# audiomeaskit.net
KiCad netlist of a schematic drawn in EAGLE
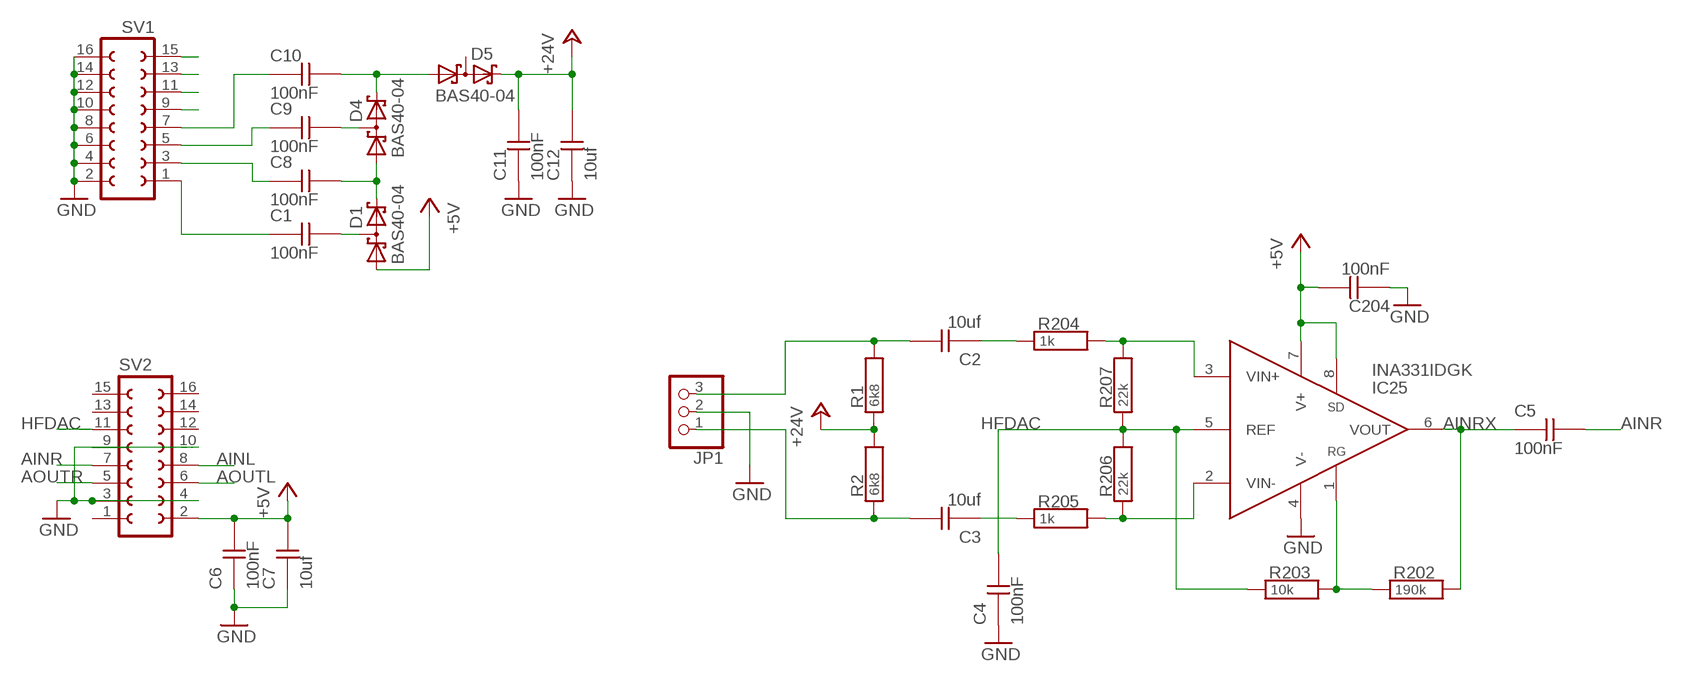
[diagram p0: schematic, sheet 1]

(export (version "E")
  (design (tool "Eeschema 10.0.6"))
  (components
    (comp (ref "C1")
      (value "100nF")
      (footprint "eagle-import:0603")
      (libsource (lib "eagle-import") (part "CAPC0603"))
    )
    (comp (ref "C2")
      (value "10uf")
      (footprint "eagle-import:0805")
      (libsource (lib "eagle-import") (part "CAPC0805"))
    )
    (comp (ref "C3")
      (value "10uf")
      (footprint "eagle-import:0805")
      (libsource (lib "eagle-import") (part "CAPC0805"))
    )
    (comp (ref "C4")
      (value "100nF")
      (footprint "eagle-import:0603")
      (libsource (lib "eagle-import") (part "CAPC0603"))
    )
    (comp (ref "C5")
      (value "100nF")
      (footprint "eagle-import:0603")
      (libsource (lib "eagle-import") (part "CAPC0603"))
    )
    (comp (ref "C6")
      (value "100nF")
      (footprint "eagle-import:0603")
      (libsource (lib "eagle-import") (part "CAPC0603"))
    )
    (comp (ref "C7")
      (value "10uf")
      (footprint "eagle-import:0805")
      (libsource (lib "eagle-import") (part "CAPC0805"))
    )
    (comp (ref "C8")
      (value "100nF")
      (footprint "eagle-import:0603")
      (libsource (lib "eagle-import") (part "CAPC0603"))
    )
    (comp (ref "C9")
      (value "100nF")
      (footprint "eagle-import:0603")
      (libsource (lib "eagle-import") (part "CAPC0603"))
    )
    (comp (ref "C10")
      (value "100nF")
      (footprint "eagle-import:0603")
      (libsource (lib "eagle-import") (part "CAPC0603"))
    )
    (comp (ref "C11")
      (value "100nF")
      (footprint "eagle-import:0603")
      (libsource (lib "eagle-import") (part "CAPC0603"))
    )
    (comp (ref "C12")
      (value "10uf")
      (footprint "eagle-import:0805")
      (libsource (lib "eagle-import") (part "CAPC0805"))
    )
    (comp (ref "C204")
      (value "100nF")
      (footprint "eagle-import:0402")
      (libsource (lib "eagle-import") (part "CAPC0402"))
    )
    (comp (ref "D1")
      (value "BAS40-04")
      (footprint "eagle-import:SOT23")
      (libsource (lib "eagle-import") (part "BAS40-04"))
    )
    (comp (ref "D4")
      (value "BAS40-04")
      (footprint "eagle-import:SOT23")
      (libsource (lib "eagle-import") (part "BAS40-04"))
    )
    (comp (ref "D5")
      (value "BAS40-04")
      (footprint "eagle-import:SOT23")
      (libsource (lib "eagle-import") (part "BAS40-04"))
    )
    (comp (ref "IC25")
      (value "INA331IDGK")
      (footprint "eagle-import:MSOP08")
      (libsource (lib "eagle-import") (part "INA331IDGK"))
    )
    (comp (ref "JP1")
      (value "PINHD-1X3")
      (footprint "eagle-import:1X03")
      (libsource (lib "eagle-import") (part "PINHD-1X3"))
    )
    (comp (ref "R1")
      (value "6k8")
      (footprint "eagle-import:0603")
      (libsource (lib "eagle-import") (part "RESR0603"))
    )
    (comp (ref "R2")
      (value "6k8")
      (footprint "eagle-import:0603")
      (libsource (lib "eagle-import") (part "RESR0603"))
    )
    (comp (ref "R202")
      (value "190k")
      (footprint "eagle-import:0603")
      (libsource (lib "eagle-import") (part "RESR0603"))
    )
    (comp (ref "R203")
      (value "10k")
      (footprint "eagle-import:0603")
      (libsource (lib "eagle-import") (part "RESR0603"))
    )
    (comp (ref "R204")
      (value "1k")
      (footprint "eagle-import:0603")
      (libsource (lib "eagle-import") (part "RESR0603"))
    )
    (comp (ref "R205")
      (value "1k")
      (footprint "eagle-import:0603")
      (libsource (lib "eagle-import") (part "RESR0603"))
    )
    (comp (ref "R206")
      (value "22k")
      (footprint "eagle-import:0603")
      (libsource (lib "eagle-import") (part "RESR0603"))
    )
    (comp (ref "R207")
      (value "22k")
      (footprint "eagle-import:0603")
      (libsource (lib "eagle-import") (part "RESR0603"))
    )
    (comp (ref "SV1")
      (value "FE08-2")
      (footprint "eagle-import:FE08-2")
      (libsource (lib "eagle-import") (part "FE08-2"))
    )
    (comp (ref "SV2")
      (value "FE08-2")
      (footprint "eagle-import:FE08-2")
      (libsource (lib "eagle-import") (part "FE08-2"))
    )
  )
  (nets
    (net (code "1") (name "+5V") (class "Default")
      (node (ref "C204") (pin "2") (pinfunction "2_2") (pintype "passive"))
      (node (ref "C6") (pin "2") (pinfunction "2_2") (pintype "passive"))
      (node (ref "C7") (pin "2") (pinfunction "2_2") (pintype "passive"))
      (node (ref "D1") (pin "1") (pinfunction "A1_1") (pintype "passive"))
      (node (ref "IC25") (pin "7") (pinfunction "V+_7") (pintype "power_in"))
      (node (ref "IC25") (pin "8") (pinfunction "SD_8") (pintype "input"))
      (node (ref "SV2") (pin "2") (pinfunction "2_2") (pintype "passive"))
    )
    (net (code "2") (name "+24V") (class "Default")
      (node (ref "C11") (pin "2") (pinfunction "2_2") (pintype "passive"))
      (node (ref "C12") (pin "2") (pinfunction "2_2") (pintype "passive"))
      (node (ref "D5") (pin "2") (pinfunction "C2_2") (pintype "passive"))
      (node (ref "R1") (pin "1") (pinfunction "P$1_1") (pintype "bidirectional"))
      (node (ref "R2") (pin "2") (pinfunction "P$2_2") (pintype "bidirectional"))
    )
    (net (code "3") (name "/AINL") (class "Default")
      (node (ref "SV2") (pin "8") (pinfunction "8_8") (pintype "passive"))
    )
    (net (code "4") (name "/AINR") (class "Default")
      (node (ref "C5") (pin "2") (pinfunction "2_2") (pintype "passive"))
      (node (ref "SV2") (pin "7") (pinfunction "7_7") (pintype "passive"))
    )
    (net (code "5") (name "/AINRX") (class "Default")
      (node (ref "C5") (pin "1") (pinfunction "1_1") (pintype "passive"))
      (node (ref "IC25") (pin "6") (pinfunction "VOUT_6") (pintype "output"))
      (node (ref "R202") (pin "2") (pinfunction "P$2_2") (pintype "bidirectional"))
    )
    (net (code "6") (name "/AOUTL") (class "Default")
      (node (ref "SV2") (pin "6") (pinfunction "6_6") (pintype "passive"))
    )
    (net (code "7") (name "/AOUTR") (class "Default")
      (node (ref "SV2") (pin "5") (pinfunction "5_5") (pintype "passive"))
    )
    (net (code "8") (name "/HFDAC") (class "Default")
      (node (ref "C4") (pin "2") (pinfunction "2_2") (pintype "passive"))
      (node (ref "IC25") (pin "5") (pinfunction "REF_5") (pintype "input"))
      (node (ref "R203") (pin "1") (pinfunction "P$1_1") (pintype "bidirectional"))
      (node (ref "R206") (pin "2") (pinfunction "P$2_2") (pintype "bidirectional"))
      (node (ref "R207") (pin "1") (pinfunction "P$1_1") (pintype "bidirectional"))
      (node (ref "SV2") (pin "11") (pinfunction "11_11") (pintype "passive"))
    )
    (net (code "9") (name "GND") (class "Default")
      (node (ref "C11") (pin "1") (pinfunction "1_1") (pintype "passive"))
      (node (ref "C12") (pin "1") (pinfunction "1_1") (pintype "passive"))
      (node (ref "C204") (pin "1") (pinfunction "1_1") (pintype "passive"))
      (node (ref "C4") (pin "1") (pinfunction "1_1") (pintype "passive"))
      (node (ref "C6") (pin "1") (pinfunction "1_1") (pintype "passive"))
      (node (ref "C7") (pin "1") (pinfunction "1_1") (pintype "passive"))
      (node (ref "IC25") (pin "4") (pinfunction "V-_4") (pintype "power_in"))
      (node (ref "JP1") (pin "2") (pinfunction "2_2") (pintype "passive"))
      (node (ref "SV1") (pin "10") (pinfunction "10_10") (pintype "passive"))
      (node (ref "SV1") (pin "12") (pinfunction "12_12") (pintype "passive"))
      (node (ref "SV1") (pin "14") (pinfunction "14_14") (pintype "passive"))
      (node (ref "SV1") (pin "16") (pinfunction "16_16") (pintype "passive"))
      (node (ref "SV1") (pin "2") (pinfunction "2_2") (pintype "passive"))
      (node (ref "SV1") (pin "4") (pinfunction "4_4") (pintype "passive"))
      (node (ref "SV1") (pin "6") (pinfunction "6_6") (pintype "passive"))
      (node (ref "SV1") (pin "8") (pinfunction "8_8") (pintype "passive"))
      (node (ref "SV2") (pin "10") (pinfunction "10_10") (pintype "passive"))
      (node (ref "SV2") (pin "3") (pinfunction "3_3") (pintype "passive"))
      (node (ref "SV2") (pin "4") (pinfunction "4_4") (pintype "passive"))
      (node (ref "SV2") (pin "9") (pinfunction "9_9") (pintype "passive"))
    )
    (net (code "10") (name "Net-(C1-Pad1)") (class "Default")
      (node (ref "C1") (pin "1") (pinfunction "1_1") (pintype "passive"))
      (node (ref "SV1") (pin "1") (pinfunction "1_1") (pintype "passive"))
    )
    (net (code "11") (name "Net-(C8-Pad1)") (class "Default")
      (node (ref "C8") (pin "1") (pinfunction "1_1") (pintype "passive"))
      (node (ref "SV1") (pin "3") (pinfunction "3_3") (pintype "passive"))
    )
    (net (code "12") (name "Net-(C9-Pad1)") (class "Default")
      (node (ref "C9") (pin "1") (pinfunction "1_1") (pintype "passive"))
      (node (ref "SV1") (pin "5") (pinfunction "5_5") (pintype "passive"))
    )
    (net (code "13") (name "Net-(C10-Pad1)") (class "Default")
      (node (ref "C10") (pin "1") (pinfunction "1_1") (pintype "passive"))
      (node (ref "SV1") (pin "7") (pinfunction "7_7") (pintype "passive"))
    )
    (net (code "14") (name "Net-(D1-C1A2)") (class "Default")
      (node (ref "C1") (pin "2") (pinfunction "2_2") (pintype "passive"))
      (node (ref "D1") (pin "3") (pinfunction "C1A2_3") (pintype "passive"))
    )
    (net (code "15") (name "Net-(D1-C2)") (class "Default")
      (node (ref "C8") (pin "2") (pinfunction "2_2") (pintype "passive"))
      (node (ref "D1") (pin "2") (pinfunction "C2_2") (pintype "passive"))
      (node (ref "D4") (pin "1") (pinfunction "A1_1") (pintype "passive"))
    )
    (net (code "16") (name "Net-(D4-C1A2)") (class "Default")
      (node (ref "C9") (pin "2") (pinfunction "2_2") (pintype "passive"))
      (node (ref "D4") (pin "3") (pinfunction "C1A2_3") (pintype "passive"))
    )
    (net (code "17") (name "Net-(D4-C2)") (class "Default")
      (node (ref "C10") (pin "2") (pinfunction "2_2") (pintype "passive"))
      (node (ref "D4") (pin "2") (pinfunction "C2_2") (pintype "passive"))
      (node (ref "D5") (pin "1") (pinfunction "A1_1") (pintype "passive"))
    )
    (net (code "18") (name "Net-(IC25-RG)") (class "Default")
      (node (ref "IC25") (pin "1") (pinfunction "RG_1") (pintype "passive"))
      (node (ref "R202") (pin "1") (pinfunction "P$1_1") (pintype "bidirectional"))
      (node (ref "R203") (pin "2") (pinfunction "P$2_2") (pintype "bidirectional"))
    )
    (net (code "19") (name "Net-(IC25-VIN+)") (class "Default")
      (node (ref "IC25") (pin "3") (pinfunction "VIN+_3") (pintype "input"))
      (node (ref "R204") (pin "2") (pinfunction "P$2_2") (pintype "bidirectional"))
      (node (ref "R207") (pin "2") (pinfunction "P$2_2") (pintype "bidirectional"))
    )
    (net (code "20") (name "Net-(IC25-VIN-)") (class "Default")
      (node (ref "IC25") (pin "2") (pinfunction "VIN-_2") (pintype "input"))
      (node (ref "R205") (pin "2") (pinfunction "P$2_2") (pintype "bidirectional"))
      (node (ref "R206") (pin "1") (pinfunction "P$1_1") (pintype "bidirectional"))
    )
    (net (code "21") (name "Net-(R1-P$2)") (class "Default")
      (node (ref "C2") (pin "2") (pinfunction "2_2") (pintype "passive"))
      (node (ref "JP1") (pin "3") (pinfunction "3_3") (pintype "passive"))
      (node (ref "R1") (pin "2") (pinfunction "P$2_2") (pintype "bidirectional"))
    )
    (net (code "22") (name "Net-(R2-P$1)") (class "Default")
      (node (ref "C3") (pin "2") (pinfunction "2_2") (pintype "passive"))
      (node (ref "JP1") (pin "1") (pinfunction "1_1") (pintype "passive"))
      (node (ref "R2") (pin "1") (pinfunction "P$1_1") (pintype "bidirectional"))
    )
    (net (code "23") (name "Net-(R204-P$1)") (class "Default")
      (node (ref "C2") (pin "1") (pinfunction "1_1") (pintype "passive"))
      (node (ref "R204") (pin "1") (pinfunction "P$1_1") (pintype "bidirectional"))
    )
    (net (code "24") (name "Net-(R205-P$1)") (class "Default")
      (node (ref "C3") (pin "1") (pinfunction "1_1") (pintype "passive"))
      (node (ref "R205") (pin "1") (pinfunction "P$1_1") (pintype "bidirectional"))
    )
    (net (code "25") (name "unconnected-(D5-C1A2-Pad3)") (class "Default")
      (node (ref "D5") (pin "3") (pinfunction "C1A2_3") (pintype "passive"))
    )
    (net (code "26") (name "unconnected-(SV1-Pad9)") (class "Default")
      (node (ref "SV1") (pin "9") (pinfunction "9_9") (pintype "passive"))
    )
    (net (code "27") (name "unconnected-(SV1-Pad11)") (class "Default")
      (node (ref "SV1") (pin "11") (pinfunction "11_11") (pintype "passive"))
    )
    (net (code "28") (name "unconnected-(SV1-Pad13)") (class "Default")
      (node (ref "SV1") (pin "13") (pinfunction "13_13") (pintype "passive"))
    )
    (net (code "29") (name "unconnected-(SV1-Pad15)") (class "Default")
      (node (ref "SV1") (pin "15") (pinfunction "15_15") (pintype "passive"))
    )
    (net (code "30") (name "unconnected-(SV2-Pad1)") (class "Default")
      (node (ref "SV2") (pin "1") (pinfunction "1_1") (pintype "passive"))
    )
    (net (code "31") (name "unconnected-(SV2-Pad12)") (class "Default")
      (node (ref "SV2") (pin "12") (pinfunction "12_12") (pintype "passive"))
    )
    (net (code "32") (name "unconnected-(SV2-Pad13)") (class "Default")
      (node (ref "SV2") (pin "13") (pinfunction "13_13") (pintype "passive"))
    )
    (net (code "33") (name "unconnected-(SV2-Pad14)") (class "Default")
      (node (ref "SV2") (pin "14") (pinfunction "14_14") (pintype "passive"))
    )
    (net (code "34") (name "unconnected-(SV2-Pad15)") (class "Default")
      (node (ref "SV2") (pin "15") (pinfunction "15_15") (pintype "passive"))
    )
    (net (code "35") (name "unconnected-(SV2-Pad16)") (class "Default")
      (node (ref "SV2") (pin "16") (pinfunction "16_16") (pintype "passive"))
    )
  )
)
